# Length_Tuning_Routing_with_CM.net
KiCad netlist of a schematic drawn in Altium Designer
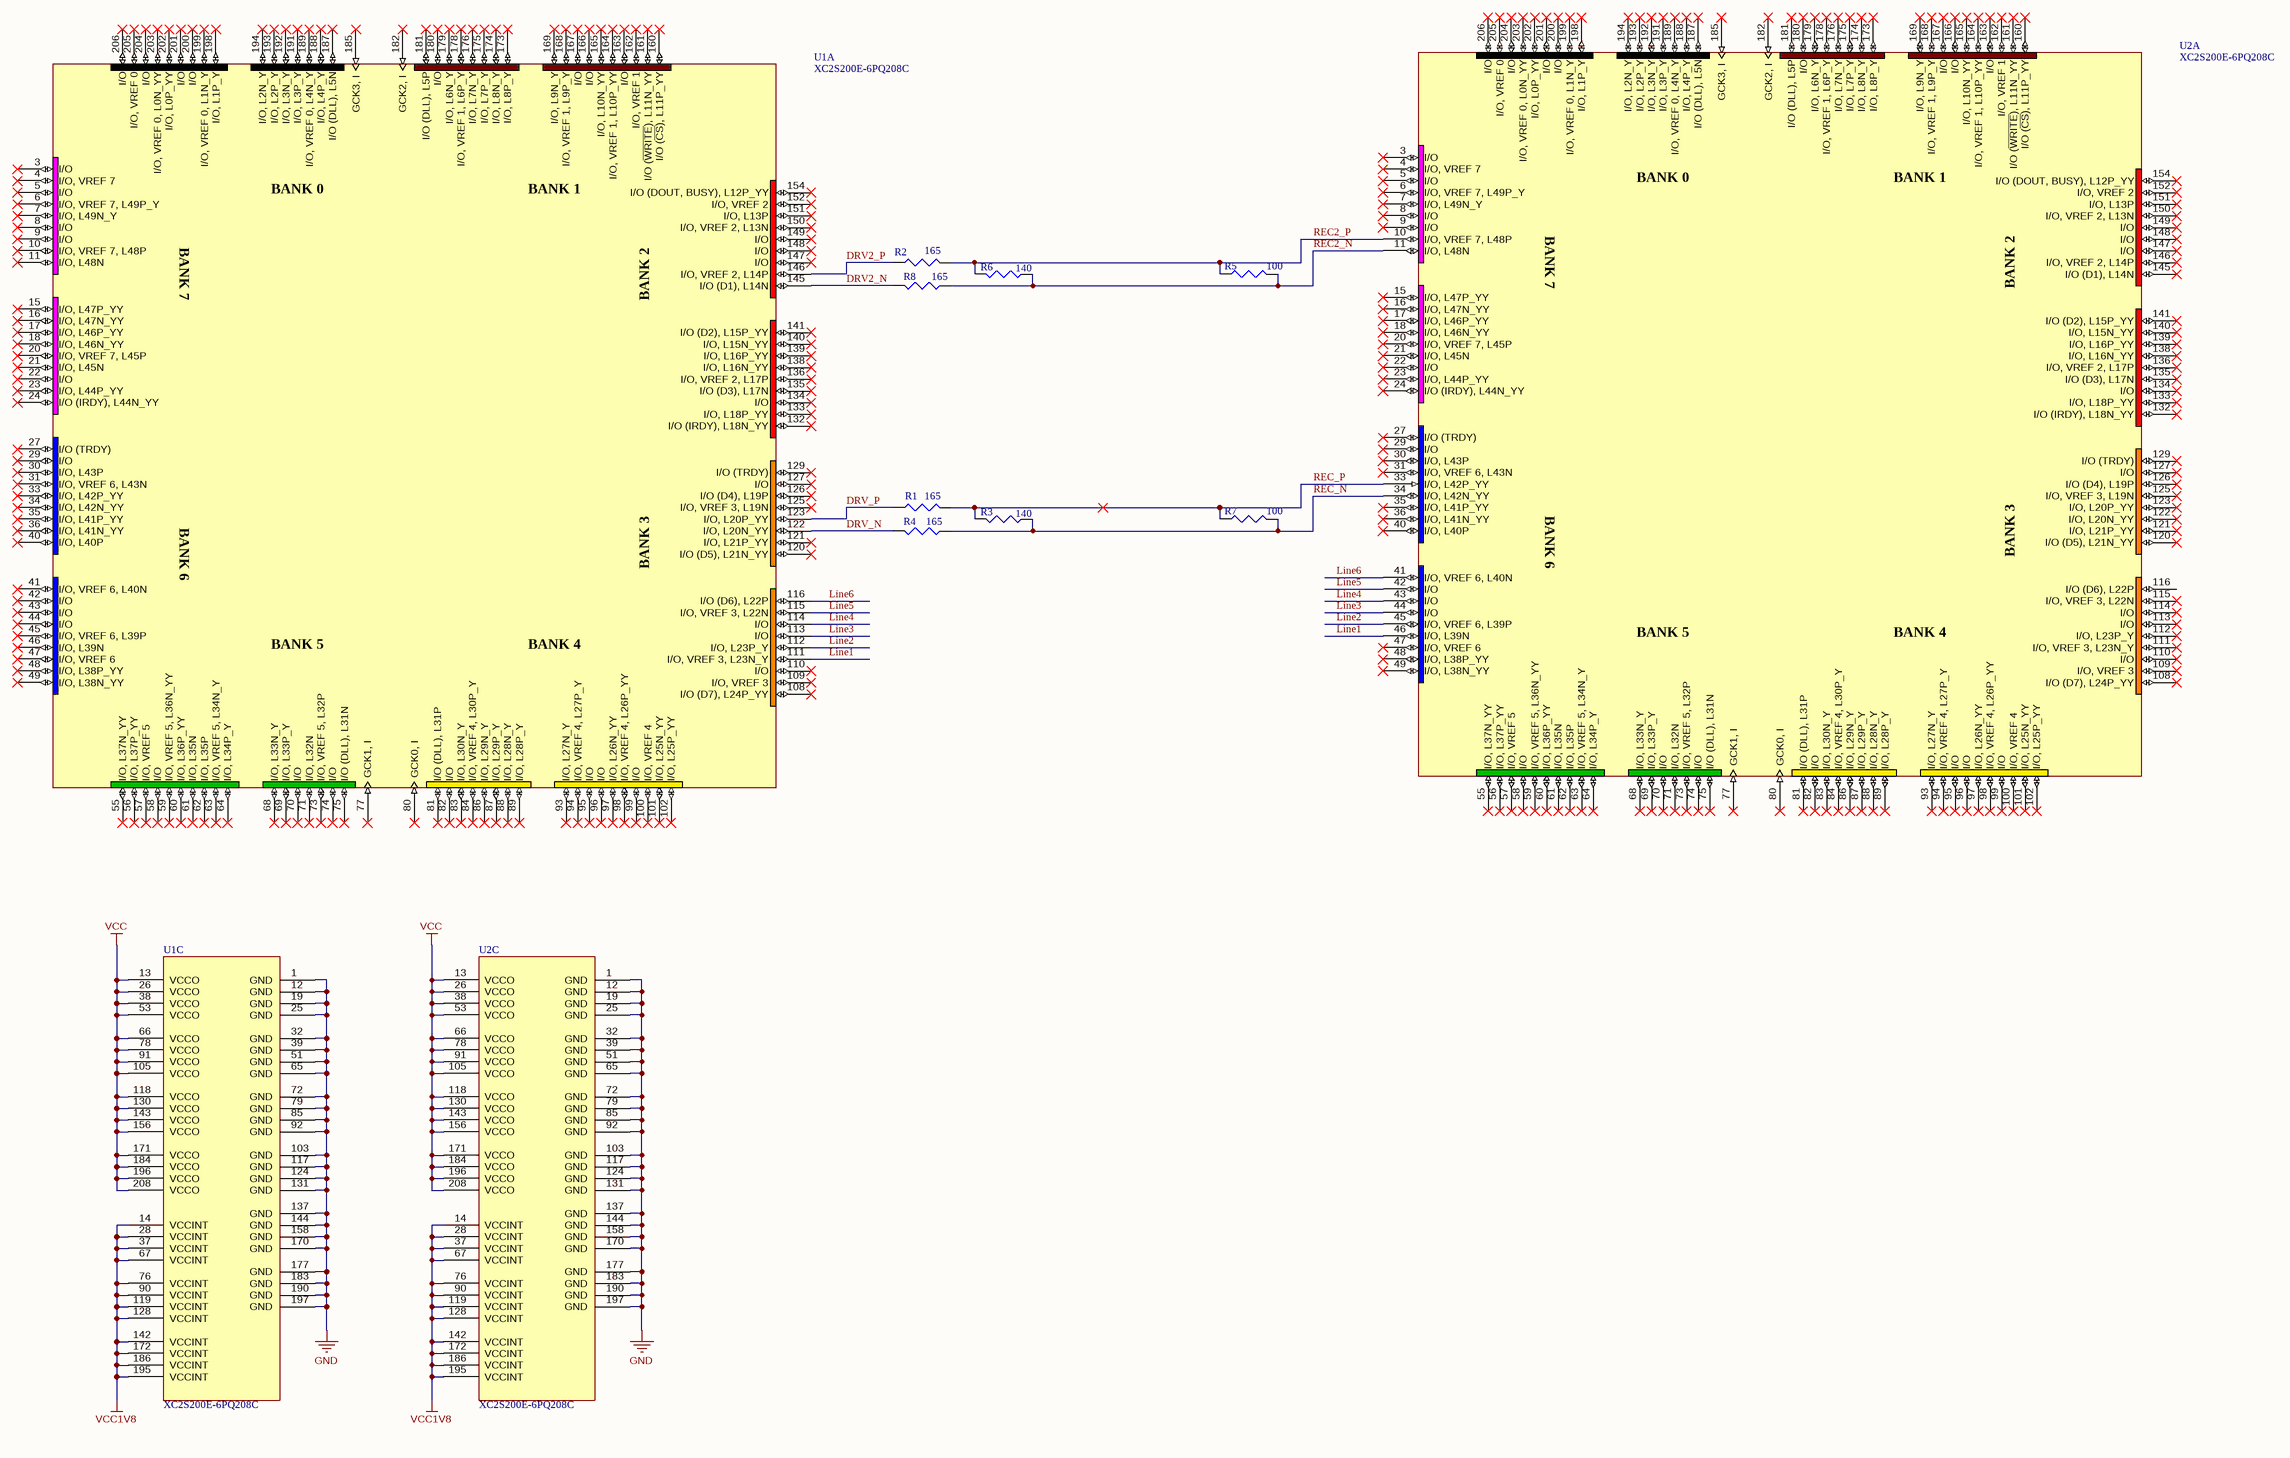
[diagram p0: Length Tuning Routing with CM.SchDoc]

(export (version "E")
  (design (tool "Eeschema 10.0.6"))
  (components
    (comp (ref "R1")
      (value "165")
      (footprint "J1-0603")
      (description "Resistor")
      (fields (field (name "Comment") "Res3") (field (name "PUBLISHER") "Altium Limited"))
      (libsource (lib "Miscellaneous Devices") (part "Res3"))
    )
    (comp (ref "R2")
      (value "165")
      (footprint "J1-0603")
      (description "Resistor")
      (fields (field (name "Comment") "Res3") (field (name "PUBLISHER") "Altium Limited"))
      (libsource (lib "Miscellaneous Devices") (part "Res3"))
    )
    (comp (ref "R3")
      (value "140")
      (footprint "J1-0603")
      (description "Resistor")
      (fields (field (name "Comment") "Res3") (field (name "PUBLISHER") "Altium Limited"))
      (libsource (lib "Miscellaneous Devices") (part "Res3"))
    )
    (comp (ref "R4")
      (value "165")
      (footprint "J1-0603")
      (description "Resistor")
      (fields (field (name "Comment") "Res3") (field (name "PUBLISHER") "Altium Limited"))
      (libsource (lib "Miscellaneous Devices") (part "Res3"))
    )
    (comp (ref "R5")
      (value "100")
      (footprint "J1-0603")
      (description "Resistor")
      (fields (field (name "Comment") "Res3") (field (name "PUBLISHER") "Altium Limited"))
      (libsource (lib "Miscellaneous Devices") (part "Res3"))
    )
    (comp (ref "R6")
      (value "140")
      (footprint "J1-0603")
      (description "Resistor")
      (fields (field (name "Comment") "Res3") (field (name "PUBLISHER") "Altium Limited"))
      (libsource (lib "Miscellaneous Devices") (part "Res3"))
    )
    (comp (ref "R7")
      (value "100")
      (footprint "J1-0603")
      (description "Resistor")
      (fields (field (name "Comment") "Res3") (field (name "PUBLISHER") "Altium Limited"))
      (libsource (lib "Miscellaneous Devices") (part "Res3"))
    )
    (comp (ref "R8")
      (value "165")
      (footprint "J1-0603")
      (description "Resistor")
      (fields (field (name "Comment") "Res3") (field (name "PUBLISHER") "Altium Limited"))
      (libsource (lib "Miscellaneous Devices") (part "Res3"))
    )
    (comp (ref "U1")
      (value "XC2S200E-6PQ208C")
      (footprint "PQ208")
      (description "Spartan-IIE 1.8V FPGA, 208-Pin PQFP, Standard Performance, Commercial Grade")
      (fields (field (name "PUBLISHER") "Altium Limited"))
      (libsource (lib "Xilinx Spartan-IIE") (part "XC2S200E-6PQ208C"))
    )
    (comp (ref "U2")
      (value "XC2S200E-6PQ208C")
      (footprint "PQ208")
      (description "Spartan-IIE 1.8V FPGA, 208-Pin PQFP, Standard Performance, Commercial Grade")
      (fields (field (name "PUBLISHER") "Altium Limited"))
      (libsource (lib "Xilinx Spartan-IIE") (part "XC2S200E-6PQ208C"))
    )
  )
  (nets
    (net (code "1") (name "/DRV2_N") (class "Default")
      (node (ref "R8") (pin "2") (pinfunction "2_2") (pintype "passive"))
      (node (ref "U1") (pin "145") (pinfunction "I/O_(D1),_L14N_145") (pintype "bidirectional"))
    )
    (net (code "2") (name "/DRV2_P") (class "Default")
      (node (ref "R2") (pin "1") (pinfunction "1_1") (pintype "passive"))
      (node (ref "U1") (pin "146") (pinfunction "I/O,_VREF_2,_L14P_146") (pintype "bidirectional"))
    )
    (net (code "3") (name "/DRV_N") (class "Default")
      (node (ref "R4") (pin "2") (pinfunction "2_2") (pintype "passive"))
      (node (ref "U1") (pin "122") (pinfunction "I/O,_L20N_YY_122") (pintype "bidirectional"))
    )
    (net (code "4") (name "/DRV_P") (class "Default")
      (node (ref "R1") (pin "1") (pinfunction "1_1") (pintype "passive"))
      (node (ref "U1") (pin "123") (pinfunction "I/O,_L20P_YY_123") (pintype "bidirectional"))
    )
    (net (code "5") (name "/Line1") (class "Default")
      (node (ref "U1") (pin "111") (pinfunction "I/O,_VREF_3,_L23N_Y_111") (pintype "bidirectional"))
      (node (ref "U2") (pin "46") (pinfunction "I/O,_L39N_46") (pintype "bidirectional"))
    )
    (net (code "6") (name "/Line2") (class "Default")
      (node (ref "U1") (pin "112") (pinfunction "I/O,_L23P_Y_112") (pintype "bidirectional"))
      (node (ref "U2") (pin "45") (pinfunction "I/O,_VREF_6,_L39P_45") (pintype "bidirectional"))
    )
    (net (code "7") (name "/Line3") (class "Default")
      (node (ref "U1") (pin "113") (pinfunction "I/O_113") (pintype "bidirectional"))
      (node (ref "U2") (pin "44") (pinfunction "I/O_44") (pintype "bidirectional"))
    )
    (net (code "8") (name "/Line4") (class "Default")
      (node (ref "U1") (pin "114") (pinfunction "I/O_114") (pintype "bidirectional"))
      (node (ref "U2") (pin "43") (pinfunction "I/O_43") (pintype "bidirectional"))
    )
    (net (code "9") (name "/Line5") (class "Default")
      (node (ref "U1") (pin "115") (pinfunction "I/O,_VREF_3,_L22N_115") (pintype "bidirectional"))
      (node (ref "U2") (pin "42") (pinfunction "I/O_42") (pintype "bidirectional"))
    )
    (net (code "10") (name "/Line6") (class "Default")
      (node (ref "U1") (pin "116") (pinfunction "I/O_(D6),_L22P_116") (pintype "bidirectional"))
      (node (ref "U2") (pin "41") (pinfunction "I/O,_VREF_6,_L40N_41") (pintype "bidirectional"))
    )
    (net (code "11") (name "/REC2_N") (class "Default")
      (node (ref "R5") (pin "2") (pinfunction "2_2") (pintype "passive"))
      (node (ref "R6") (pin "1") (pinfunction "1_1") (pintype "passive"))
      (node (ref "R8") (pin "1") (pinfunction "1_1") (pintype "passive"))
      (node (ref "U2") (pin "11") (pinfunction "I/O,_L48N_11") (pintype "bidirectional"))
    )
    (net (code "12") (name "/REC2_P") (class "Default")
      (node (ref "R2") (pin "2") (pinfunction "2_2") (pintype "passive"))
      (node (ref "R5") (pin "1") (pinfunction "1_1") (pintype "passive"))
      (node (ref "R6") (pin "2") (pinfunction "2_2") (pintype "passive"))
      (node (ref "U2") (pin "10") (pinfunction "I/O,_VREF_7,_L48P_10") (pintype "bidirectional"))
    )
    (net (code "13") (name "/REC_N") (class "Default")
      (node (ref "R3") (pin "1") (pinfunction "1_1") (pintype "passive"))
      (node (ref "R4") (pin "1") (pinfunction "1_1") (pintype "passive"))
      (node (ref "R7") (pin "2") (pinfunction "2_2") (pintype "passive"))
      (node (ref "U2") (pin "34") (pinfunction "I/O,_L42N_YY_34") (pintype "bidirectional"))
    )
    (net (code "14") (name "/REC_P") (class "Default")
      (node (ref "R1") (pin "2") (pinfunction "2_2") (pintype "passive"))
      (node (ref "R3") (pin "2") (pinfunction "2_2") (pintype "passive"))
      (node (ref "R7") (pin "1") (pinfunction "1_1") (pintype "passive"))
      (node (ref "U2") (pin "33") (pinfunction "I/O,_L42P_YY_33") (pintype "bidirectional"))
    )
    (net (code "15") (name "GND") (class "Default")
      (node (ref "U1") (pin "1") (pinfunction "GND_1") (pintype "power_in"))
      (node (ref "U1") (pin "103") (pinfunction "GND_103") (pintype "power_in"))
      (node (ref "U1") (pin "117") (pinfunction "GND_117") (pintype "power_in"))
      (node (ref "U1") (pin "12") (pinfunction "GND_12") (pintype "power_in"))
      (node (ref "U1") (pin "124") (pinfunction "GND_124") (pintype "power_in"))
      (node (ref "U1") (pin "131") (pinfunction "GND_131") (pintype "power_in"))
      (node (ref "U1") (pin "137") (pinfunction "GND_137") (pintype "power_in"))
      (node (ref "U1") (pin "144") (pinfunction "GND_144") (pintype "power_in"))
      (node (ref "U1") (pin "158") (pinfunction "GND_158") (pintype "power_in"))
      (node (ref "U1") (pin "170") (pinfunction "GND_170") (pintype "power_in"))
      (node (ref "U1") (pin "177") (pinfunction "GND_177") (pintype "power_in"))
      (node (ref "U1") (pin "183") (pinfunction "GND_183") (pintype "power_in"))
      (node (ref "U1") (pin "19") (pinfunction "GND_19") (pintype "power_in"))
      (node (ref "U1") (pin "190") (pinfunction "GND_190") (pintype "power_in"))
      (node (ref "U1") (pin "197") (pinfunction "GND_197") (pintype "power_in"))
      (node (ref "U1") (pin "25") (pinfunction "GND_25") (pintype "power_in"))
      (node (ref "U1") (pin "32") (pinfunction "GND_32") (pintype "power_in"))
      (node (ref "U1") (pin "39") (pinfunction "GND_39") (pintype "power_in"))
      (node (ref "U1") (pin "51") (pinfunction "GND_51") (pintype "power_in"))
      (node (ref "U1") (pin "65") (pinfunction "GND_65") (pintype "power_in"))
      (node (ref "U1") (pin "72") (pinfunction "GND_72") (pintype "power_in"))
      (node (ref "U1") (pin "79") (pinfunction "GND_79") (pintype "power_in"))
      (node (ref "U1") (pin "85") (pinfunction "GND_85") (pintype "power_in"))
      (node (ref "U1") (pin "92") (pinfunction "GND_92") (pintype "power_in"))
      (node (ref "U2") (pin "1") (pinfunction "GND_1") (pintype "power_in"))
      (node (ref "U2") (pin "103") (pinfunction "GND_103") (pintype "power_in"))
      (node (ref "U2") (pin "117") (pinfunction "GND_117") (pintype "power_in"))
      (node (ref "U2") (pin "12") (pinfunction "GND_12") (pintype "power_in"))
      (node (ref "U2") (pin "124") (pinfunction "GND_124") (pintype "power_in"))
      (node (ref "U2") (pin "131") (pinfunction "GND_131") (pintype "power_in"))
      (node (ref "U2") (pin "137") (pinfunction "GND_137") (pintype "power_in"))
      (node (ref "U2") (pin "144") (pinfunction "GND_144") (pintype "power_in"))
      (node (ref "U2") (pin "158") (pinfunction "GND_158") (pintype "power_in"))
      (node (ref "U2") (pin "170") (pinfunction "GND_170") (pintype "power_in"))
      (node (ref "U2") (pin "177") (pinfunction "GND_177") (pintype "power_in"))
      (node (ref "U2") (pin "183") (pinfunction "GND_183") (pintype "power_in"))
      (node (ref "U2") (pin "19") (pinfunction "GND_19") (pintype "power_in"))
      (node (ref "U2") (pin "190") (pinfunction "GND_190") (pintype "power_in"))
      (node (ref "U2") (pin "197") (pinfunction "GND_197") (pintype "power_in"))
      (node (ref "U2") (pin "25") (pinfunction "GND_25") (pintype "power_in"))
      (node (ref "U2") (pin "32") (pinfunction "GND_32") (pintype "power_in"))
      (node (ref "U2") (pin "39") (pinfunction "GND_39") (pintype "power_in"))
      (node (ref "U2") (pin "51") (pinfunction "GND_51") (pintype "power_in"))
      (node (ref "U2") (pin "65") (pinfunction "GND_65") (pintype "power_in"))
      (node (ref "U2") (pin "72") (pinfunction "GND_72") (pintype "power_in"))
      (node (ref "U2") (pin "79") (pinfunction "GND_79") (pintype "power_in"))
      (node (ref "U2") (pin "85") (pinfunction "GND_85") (pintype "power_in"))
      (node (ref "U2") (pin "92") (pinfunction "GND_92") (pintype "power_in"))
    )
    (net (code "16") (name "VCC") (class "Default")
      (node (ref "U1") (pin "105") (pinfunction "VCCO_105") (pintype "power_in"))
      (node (ref "U1") (pin "118") (pinfunction "VCCO_118") (pintype "power_in"))
      (node (ref "U1") (pin "13") (pinfunction "VCCO_13") (pintype "power_in"))
      (node (ref "U1") (pin "130") (pinfunction "VCCO_130") (pintype "power_in"))
      (node (ref "U1") (pin "143") (pinfunction "VCCO_143") (pintype "power_in"))
      (node (ref "U1") (pin "156") (pinfunction "VCCO_156") (pintype "power_in"))
      (node (ref "U1") (pin "171") (pinfunction "VCCO_171") (pintype "power_in"))
      (node (ref "U1") (pin "184") (pinfunction "VCCO_184") (pintype "power_in"))
      (node (ref "U1") (pin "196") (pinfunction "VCCO_196") (pintype "power_in"))
      (node (ref "U1") (pin "208") (pinfunction "VCCO_208") (pintype "power_in"))
      (node (ref "U1") (pin "26") (pinfunction "VCCO_26") (pintype "power_in"))
      (node (ref "U1") (pin "38") (pinfunction "VCCO_38") (pintype "power_in"))
      (node (ref "U1") (pin "53") (pinfunction "VCCO_53") (pintype "power_in"))
      (node (ref "U1") (pin "66") (pinfunction "VCCO_66") (pintype "power_in"))
      (node (ref "U1") (pin "78") (pinfunction "VCCO_78") (pintype "power_in"))
      (node (ref "U1") (pin "91") (pinfunction "VCCO_91") (pintype "power_in"))
      (node (ref "U2") (pin "105") (pinfunction "VCCO_105") (pintype "power_in"))
      (node (ref "U2") (pin "118") (pinfunction "VCCO_118") (pintype "power_in"))
      (node (ref "U2") (pin "13") (pinfunction "VCCO_13") (pintype "power_in"))
      (node (ref "U2") (pin "130") (pinfunction "VCCO_130") (pintype "power_in"))
      (node (ref "U2") (pin "143") (pinfunction "VCCO_143") (pintype "power_in"))
      (node (ref "U2") (pin "156") (pinfunction "VCCO_156") (pintype "power_in"))
      (node (ref "U2") (pin "171") (pinfunction "VCCO_171") (pintype "power_in"))
      (node (ref "U2") (pin "184") (pinfunction "VCCO_184") (pintype "power_in"))
      (node (ref "U2") (pin "196") (pinfunction "VCCO_196") (pintype "power_in"))
      (node (ref "U2") (pin "208") (pinfunction "VCCO_208") (pintype "power_in"))
      (node (ref "U2") (pin "26") (pinfunction "VCCO_26") (pintype "power_in"))
      (node (ref "U2") (pin "38") (pinfunction "VCCO_38") (pintype "power_in"))
      (node (ref "U2") (pin "53") (pinfunction "VCCO_53") (pintype "power_in"))
      (node (ref "U2") (pin "66") (pinfunction "VCCO_66") (pintype "power_in"))
      (node (ref "U2") (pin "78") (pinfunction "VCCO_78") (pintype "power_in"))
      (node (ref "U2") (pin "91") (pinfunction "VCCO_91") (pintype "power_in"))
    )
    (net (code "17") (name "VCC1V8") (class "Default")
      (node (ref "U1") (pin "119") (pinfunction "VCCINT_119") (pintype "power_in"))
      (node (ref "U1") (pin "128") (pinfunction "VCCINT_128") (pintype "power_in"))
      (node (ref "U1") (pin "14") (pinfunction "VCCINT_14") (pintype "power_in"))
      (node (ref "U1") (pin "142") (pinfunction "VCCINT_142") (pintype "power_in"))
      (node (ref "U1") (pin "172") (pinfunction "VCCINT_172") (pintype "power_in"))
      (node (ref "U1") (pin "186") (pinfunction "VCCINT_186") (pintype "power_in"))
      (node (ref "U1") (pin "195") (pinfunction "VCCINT_195") (pintype "power_in"))
      (node (ref "U1") (pin "28") (pinfunction "VCCINT_28") (pintype "power_in"))
      (node (ref "U1") (pin "37") (pinfunction "VCCINT_37") (pintype "power_in"))
      (node (ref "U1") (pin "67") (pinfunction "VCCINT_67") (pintype "power_in"))
      (node (ref "U1") (pin "76") (pinfunction "VCCINT_76") (pintype "power_in"))
      (node (ref "U1") (pin "90") (pinfunction "VCCINT_90") (pintype "power_in"))
      (node (ref "U2") (pin "119") (pinfunction "VCCINT_119") (pintype "power_in"))
      (node (ref "U2") (pin "128") (pinfunction "VCCINT_128") (pintype "power_in"))
      (node (ref "U2") (pin "14") (pinfunction "VCCINT_14") (pintype "power_in"))
      (node (ref "U2") (pin "142") (pinfunction "VCCINT_142") (pintype "power_in"))
      (node (ref "U2") (pin "172") (pinfunction "VCCINT_172") (pintype "power_in"))
      (node (ref "U2") (pin "186") (pinfunction "VCCINT_186") (pintype "power_in"))
      (node (ref "U2") (pin "195") (pinfunction "VCCINT_195") (pintype "power_in"))
      (node (ref "U2") (pin "28") (pinfunction "VCCINT_28") (pintype "power_in"))
      (node (ref "U2") (pin "37") (pinfunction "VCCINT_37") (pintype "power_in"))
      (node (ref "U2") (pin "67") (pinfunction "VCCINT_67") (pintype "power_in"))
      (node (ref "U2") (pin "76") (pinfunction "VCCINT_76") (pintype "power_in"))
      (node (ref "U2") (pin "90") (pinfunction "VCCINT_90") (pintype "power_in"))
    )
    (net (code "18") (name "unconnected-(U1A-GCK0,_I-Pad80)") (class "Default")
      (node (ref "U1") (pin "80") (pinfunction "GCK0,_I_80") (pintype "input+no_connect"))
    )
    (net (code "19") (name "unconnected-(U1A-GCK1,_I-Pad77)") (class "Default")
      (node (ref "U1") (pin "77") (pinfunction "GCK1,_I_77") (pintype "input+no_connect"))
    )
    (net (code "20") (name "unconnected-(U1A-GCK2,_I-Pad182)") (class "Default")
      (node (ref "U1") (pin "182") (pinfunction "GCK2,_I_182") (pintype "input+no_connect"))
    )
    (net (code "21") (name "unconnected-(U1A-GCK3,_I-Pad185)") (class "Default")
      (node (ref "U1") (pin "185") (pinfunction "GCK3,_I_185") (pintype "input+no_connect"))
    )
    (net (code "22") (name "unconnected-(U1A-I{slash}O,_L0P_YY-Pad202)") (class "Default")
      (node (ref "U1") (pin "202") (pinfunction "I/O,_L0P_YY_202") (pintype "bidirectional+no_connect"))
    )
    (net (code "23") (name "unconnected-(U1A-I{slash}O,_L1P_Y-Pad198)") (class "Default")
      (node (ref "U1") (pin "198") (pinfunction "I/O,_L1P_Y_198") (pintype "bidirectional+no_connect"))
    )
    (net (code "24") (name "unconnected-(U1A-I{slash}O,_L2N_Y-Pad194)") (class "Default")
      (node (ref "U1") (pin "194") (pinfunction "I/O,_L2N_Y_194") (pintype "bidirectional+no_connect"))
    )
    (net (code "25") (name "unconnected-(U1A-I{slash}O,_L2P_Y-Pad193)") (class "Default")
      (node (ref "U1") (pin "193") (pinfunction "I/O,_L2P_Y_193") (pintype "bidirectional+no_connect"))
    )
    (net (code "26") (name "unconnected-(U1A-I{slash}O,_L3N_Y-Pad192)") (class "Default")
      (node (ref "U1") (pin "192") (pinfunction "I/O,_L3N_Y_192") (pintype "bidirectional+no_connect"))
    )
    (net (code "27") (name "unconnected-(U1A-I{slash}O,_L3P_Y-Pad191)") (class "Default")
      (node (ref "U1") (pin "191") (pinfunction "I/O,_L3P_Y_191") (pintype "bidirectional+no_connect"))
    )
    (net (code "28") (name "unconnected-(U1A-I{slash}O,_L4P_Y-Pad188)") (class "Default")
      (node (ref "U1") (pin "188") (pinfunction "I/O,_L4P_Y_188") (pintype "bidirectional+no_connect"))
    )
    (net (code "29") (name "unconnected-(U1A-I{slash}O,_L6N_Y-Pad179)") (class "Default")
      (node (ref "U1") (pin "179") (pinfunction "I/O,_L6N_Y_179") (pintype "bidirectional+no_connect"))
    )
    (net (code "30") (name "unconnected-(U1A-I{slash}O,_L7N_Y-Pad176)") (class "Default")
      (node (ref "U1") (pin "176") (pinfunction "I/O,_L7N_Y_176") (pintype "bidirectional+no_connect"))
    )
    (net (code "31") (name "unconnected-(U1A-I{slash}O,_L7P_Y-Pad175)") (class "Default")
      (node (ref "U1") (pin "175") (pinfunction "I/O,_L7P_Y_175") (pintype "bidirectional+no_connect"))
    )
    (net (code "32") (name "unconnected-(U1A-I{slash}O,_L8N_Y-Pad174)") (class "Default")
      (node (ref "U1") (pin "174") (pinfunction "I/O,_L8N_Y_174") (pintype "bidirectional+no_connect"))
    )
    (net (code "33") (name "unconnected-(U1A-I{slash}O,_L8P_Y-Pad173)") (class "Default")
      (node (ref "U1") (pin "173") (pinfunction "I/O,_L8P_Y_173") (pintype "bidirectional+no_connect"))
    )
    (net (code "34") (name "unconnected-(U1A-I{slash}O,_L9N_Y-Pad169)") (class "Default")
      (node (ref "U1") (pin "169") (pinfunction "I/O,_L9N_Y_169") (pintype "bidirectional+no_connect"))
    )
    (net (code "35") (name "unconnected-(U1A-I{slash}O,_L10N_YY-Pad165)") (class "Default")
      (node (ref "U1") (pin "165") (pinfunction "I/O,_L10N_YY_165") (pintype "bidirectional+no_connect"))
    )
    (net (code "36") (name "unconnected-(U1A-I{slash}O,_L13P-Pad151)") (class "Default")
      (node (ref "U1") (pin "151") (pinfunction "I/O,_L13P_151") (pintype "bidirectional+no_connect"))
    )
    (net (code "37") (name "unconnected-(U1A-I{slash}O,_L15N_YY-Pad140)") (class "Default")
      (node (ref "U1") (pin "140") (pinfunction "I/O,_L15N_YY_140") (pintype "bidirectional+no_connect"))
    )
    (net (code "38") (name "unconnected-(U1A-I{slash}O,_L16N_YY-Pad138)") (class "Default")
      (node (ref "U1") (pin "138") (pinfunction "I/O,_L16N_YY_138") (pintype "bidirectional+no_connect"))
    )
    (net (code "39") (name "unconnected-(U1A-I{slash}O,_L16P_YY-Pad139)") (class "Default")
      (node (ref "U1") (pin "139") (pinfunction "I/O,_L16P_YY_139") (pintype "bidirectional+no_connect"))
    )
    (net (code "40") (name "unconnected-(U1A-I{slash}O,_L18P_YY-Pad133)") (class "Default")
      (node (ref "U1") (pin "133") (pinfunction "I/O,_L18P_YY_133") (pintype "bidirectional+no_connect"))
    )
    (net (code "41") (name "unconnected-(U1A-I{slash}O,_L21P_YY-Pad121)") (class "Default")
      (node (ref "U1") (pin "121") (pinfunction "I/O,_L21P_YY_121") (pintype "bidirectional+no_connect"))
    )
    (net (code "42") (name "unconnected-(U1A-I{slash}O,_L25N_YY-Pad101)") (class "Default")
      (node (ref "U1") (pin "101") (pinfunction "I/O,_L25N_YY_101") (pintype "bidirectional+no_connect"))
    )
    (net (code "43") (name "unconnected-(U1A-I{slash}O,_L25P_YY-Pad102)") (class "Default")
      (node (ref "U1") (pin "102") (pinfunction "I/O,_L25P_YY_102") (pintype "bidirectional+no_connect"))
    )
    (net (code "44") (name "unconnected-(U1A-I{slash}O,_L26N_YY-Pad97)") (class "Default")
      (node (ref "U1") (pin "97") (pinfunction "I/O,_L26N_YY_97") (pintype "bidirectional+no_connect"))
    )
    (net (code "45") (name "unconnected-(U1A-I{slash}O,_L27N_Y-Pad93)") (class "Default")
      (node (ref "U1") (pin "93") (pinfunction "I/O,_L27N_Y_93") (pintype "bidirectional+no_connect"))
    )
    (net (code "46") (name "unconnected-(U1A-I{slash}O,_L28N_Y-Pad88)") (class "Default")
      (node (ref "U1") (pin "88") (pinfunction "I/O,_L28N_Y_88") (pintype "bidirectional+no_connect"))
    )
    (net (code "47") (name "unconnected-(U1A-I{slash}O,_L28P_Y-Pad89)") (class "Default")
      (node (ref "U1") (pin "89") (pinfunction "I/O,_L28P_Y_89") (pintype "bidirectional+no_connect"))
    )
    (net (code "48") (name "unconnected-(U1A-I{slash}O,_L29N_Y-Pad86)") (class "Default")
      (node (ref "U1") (pin "86") (pinfunction "I/O,_L29N_Y_86") (pintype "bidirectional+no_connect"))
    )
    (net (code "49") (name "unconnected-(U1A-I{slash}O,_L29P_Y-Pad87)") (class "Default")
      (node (ref "U1") (pin "87") (pinfunction "I/O,_L29P_Y_87") (pintype "bidirectional+no_connect"))
    )
    (net (code "50") (name "unconnected-(U1A-I{slash}O,_L30N_Y-Pad83)") (class "Default")
      (node (ref "U1") (pin "83") (pinfunction "I/O,_L30N_Y_83") (pintype "bidirectional+no_connect"))
    )
    (net (code "51") (name "unconnected-(U1A-I{slash}O,_L32N-Pad71)") (class "Default")
      (node (ref "U1") (pin "71") (pinfunction "I/O,_L32N_71") (pintype "bidirectional+no_connect"))
    )
    (net (code "52") (name "unconnected-(U1A-I{slash}O,_L33N_Y-Pad68)") (class "Default")
      (node (ref "U1") (pin "68") (pinfunction "I/O,_L33N_Y_68") (pintype "bidirectional+no_connect"))
    )
    (net (code "53") (name "unconnected-(U1A-I{slash}O,_L33P_Y-Pad69)") (class "Default")
      (node (ref "U1") (pin "69") (pinfunction "I/O,_L33P_Y_69") (pintype "bidirectional+no_connect"))
    )
    (net (code "54") (name "unconnected-(U1A-I{slash}O,_L34P_Y-Pad64)") (class "Default")
      (node (ref "U1") (pin "64") (pinfunction "I/O,_L34P_Y_64") (pintype "bidirectional+no_connect"))
    )
    (net (code "55") (name "unconnected-(U1A-I{slash}O,_L35N-Pad61)") (class "Default")
      (node (ref "U1") (pin "61") (pinfunction "I/O,_L35N_61") (pintype "bidirectional+no_connect"))
    )
    (net (code "56") (name "unconnected-(U1A-I{slash}O,_L35P-Pad62)") (class "Default")
      (node (ref "U1") (pin "62") (pinfunction "I/O,_L35P_62") (pintype "bidirectional+no_connect"))
    )
    (net (code "57") (name "unconnected-(U1A-I{slash}O,_L36P_YY-Pad60)") (class "Default")
      (node (ref "U1") (pin "60") (pinfunction "I/O,_L36P_YY_60") (pintype "bidirectional+no_connect"))
    )
    (net (code "58") (name "unconnected-(U1A-I{slash}O,_L37N_YY-Pad55)") (class "Default")
      (node (ref "U1") (pin "55") (pinfunction "I/O,_L37N_YY_55") (pintype "bidirectional+no_connect"))
    )
    (net (code "59") (name "unconnected-(U1A-I{slash}O,_L37P_YY-Pad56)") (class "Default")
      (node (ref "U1") (pin "56") (pinfunction "I/O,_L37P_YY_56") (pintype "bidirectional+no_connect"))
    )
    (net (code "60") (name "unconnected-(U1A-I{slash}O,_L38N_YY-Pad49)") (class "Default")
      (node (ref "U1") (pin "49") (pinfunction "I/O,_L38N_YY_49") (pintype "bidirectional+no_connect"))
    )
    (net (code "61") (name "unconnected-(U1A-I{slash}O,_L38P_YY-Pad48)") (class "Default")
      (node (ref "U1") (pin "48") (pinfunction "I/O,_L38P_YY_48") (pintype "bidirectional+no_connect"))
    )
    (net (code "62") (name "unconnected-(U1A-I{slash}O,_L39N-Pad46)") (class "Default")
      (node (ref "U1") (pin "46") (pinfunction "I/O,_L39N_46") (pintype "bidirectional+no_connect"))
    )
    (net (code "63") (name "unconnected-(U1A-I{slash}O,_L40P-Pad40)") (class "Default")
      (node (ref "U1") (pin "40") (pinfunction "I/O,_L40P_40") (pintype "bidirectional+no_connect"))
    )
    (net (code "64") (name "unconnected-(U1A-I{slash}O,_L41N_YY-Pad36)") (class "Default")
      (node (ref "U1") (pin "36") (pinfunction "I/O,_L41N_YY_36") (pintype "bidirectional+no_connect"))
    )
    (net (code "65") (name "unconnected-(U1A-I{slash}O,_L41P_YY-Pad35)") (class "Default")
      (node (ref "U1") (pin "35") (pinfunction "I/O,_L41P_YY_35") (pintype "bidirectional+no_connect"))
    )
    (net (code "66") (name "unconnected-(U1A-I{slash}O,_L42N_YY-Pad34)") (class "Default")
      (node (ref "U1") (pin "34") (pinfunction "I/O,_L42N_YY_34") (pintype "bidirectional+no_connect"))
    )
    (net (code "67") (name "unconnected-(U1A-I{slash}O,_L42P_YY-Pad33)") (class "Default")
      (node (ref "U1") (pin "33") (pinfunction "I/O,_L42P_YY_33") (pintype "bidirectional+no_connect"))
    )
    (net (code "68") (name "unconnected-(U1A-I{slash}O,_L43P-Pad30)") (class "Default")
      (node (ref "U1") (pin "30") (pinfunction "I/O,_L43P_30") (pintype "bidirectional+no_connect"))
    )
    (net (code "69") (name "unconnected-(U1A-I{slash}O,_L44P_YY-Pad23)") (class "Default")
      (node (ref "U1") (pin "23") (pinfunction "I/O,_L44P_YY_23") (pintype "bidirectional+no_connect"))
    )
    (net (code "70") (name "unconnected-(U1A-I{slash}O,_L45N-Pad21)") (class "Default")
      (node (ref "U1") (pin "21") (pinfunction "I/O,_L45N_21") (pintype "bidirectional+no_connect"))
    )
    (net (code "71") (name "unconnected-(U1A-I{slash}O,_L46N_YY-Pad18)") (class "Default")
      (node (ref "U1") (pin "18") (pinfunction "I/O,_L46N_YY_18") (pintype "bidirectional+no_connect"))
    )
    (net (code "72") (name "unconnected-(U1A-I{slash}O,_L46P_YY-Pad17)") (class "Default")
      (node (ref "U1") (pin "17") (pinfunction "I/O,_L46P_YY_17") (pintype "bidirectional+no_connect"))
    )
    (net (code "73") (name "unconnected-(U1A-I{slash}O,_L47N_YY-Pad16)") (class "Default")
      (node (ref "U1") (pin "16") (pinfunction "I/O,_L47N_YY_16") (pintype "bidirectional+no_connect"))
    )
    (net (code "74") (name "unconnected-(U1A-I{slash}O,_L47P_YY-Pad15)") (class "Default")
      (node (ref "U1") (pin "15") (pinfunction "I/O,_L47P_YY_15") (pintype "bidirectional+no_connect"))
    )
    (net (code "75") (name "unconnected-(U1A-I{slash}O,_L48N-Pad11)") (class "Default")
      (node (ref "U1") (pin "11") (pinfunction "I/O,_L48N_11") (pintype "bidirectional+no_connect"))
    )
    (net (code "76") (name "unconnected-(U1A-I{slash}O,_L49N_Y-Pad7)") (class "Default")
      (node (ref "U1") (pin "7") (pinfunction "I/O,_L49N_Y_7") (pintype "bidirectional+no_connect"))
    )
    (net (code "77") (name "unconnected-(U1A-I{slash}O,_VREF_0,_L0N_YY-Pad203)") (class "Default")
      (node (ref "U1") (pin "203") (pinfunction "I/O,_VREF_0,_L0N_YY_203") (pintype "bidirectional+no_connect"))
    )
    (net (code "78") (name "unconnected-(U1A-I{slash}O,_VREF_0,_L1N_Y-Pad199)") (class "Default")
      (node (ref "U1") (pin "199") (pinfunction "I/O,_VREF_0,_L1N_Y_199") (pintype "bidirectional+no_connect"))
    )
    (net (code "79") (name "unconnected-(U1A-I{slash}O,_VREF_0,_L4N_Y-Pad189)") (class "Default")
      (node (ref "U1") (pin "189") (pinfunction "I/O,_VREF_0,_L4N_Y_189") (pintype "bidirectional+no_connect"))
    )
    (net (code "80") (name "unconnected-(U1A-I{slash}O,_VREF_0-Pad205)") (class "Default")
      (node (ref "U1") (pin "205") (pinfunction "I/O,_VREF_0_205") (pintype "bidirectional+no_connect"))
    )
    (net (code "81") (name "unconnected-(U1A-I{slash}O,_VREF_1,_L6P_Y-Pad178)") (class "Default")
      (node (ref "U1") (pin "178") (pinfunction "I/O,_VREF_1,_L6P_Y_178") (pintype "bidirectional+no_connect"))
    )
    (net (code "82") (name "unconnected-(U1A-I{slash}O,_VREF_1,_L9P_Y-Pad168)") (class "Default")
      (node (ref "U1") (pin "168") (pinfunction "I/O,_VREF_1,_L9P_Y_168") (pintype "bidirectional+no_connect"))
    )
    (net (code "83") (name "unconnected-(U1A-I{slash}O,_VREF_1,_L10P_YY-Pad164)") (class "Default")
      (node (ref "U1") (pin "164") (pinfunction "I/O,_VREF_1,_L10P_YY_164") (pintype "bidirectional+no_connect"))
    )
    (net (code "84") (name "unconnected-(U1A-I{slash}O,_VREF_1-Pad162)") (class "Default")
      (node (ref "U1") (pin "162") (pinfunction "I/O,_VREF_1_162") (pintype "bidirectional+no_connect"))
    )
    (net (code "85") (name "unconnected-(U1A-I{slash}O,_VREF_2,_L13N-Pad150)") (class "Default")
      (node (ref "U1") (pin "150") (pinfunction "I/O,_VREF_2,_L13N_150") (pintype "bidirectional+no_connect"))
    )
    (net (code "86") (name "unconnected-(U1A-I{slash}O,_VREF_2,_L17P-Pad136)") (class "Default")
      (node (ref "U1") (pin "136") (pinfunction "I/O,_VREF_2,_L17P_136") (pintype "bidirectional+no_connect"))
    )
    (net (code "87") (name "unconnected-(U1A-I{slash}O,_VREF_2-Pad152)") (class "Default")
      (node (ref "U1") (pin "152") (pinfunction "I/O,_VREF_2_152") (pintype "bidirectional+no_connect"))
    )
    (net (code "88") (name "unconnected-(U1A-I{slash}O,_VREF_3,_L19N-Pad125)") (class "Default")
      (node (ref "U1") (pin "125") (pinfunction "I/O,_VREF_3,_L19N_125") (pintype "bidirectional+no_connect"))
    )
    (net (code "89") (name "unconnected-(U1A-I{slash}O,_VREF_3-Pad109)") (class "Default")
      (node (ref "U1") (pin "109") (pinfunction "I/O,_VREF_3_109") (pintype "bidirectional+no_connect"))
    )
    (net (code "90") (name "unconnected-(U1A-I{slash}O,_VREF_4,_L26P_YY-Pad98)") (class "Default")
      (node (ref "U1") (pin "98") (pinfunction "I/O,_VREF_4,_L26P_YY_98") (pintype "bidirectional+no_connect"))
    )
    (net (code "91") (name "unconnected-(U1A-I{slash}O,_VREF_4,_L27P_Y-Pad94)") (class "Default")
      (node (ref "U1") (pin "94") (pinfunction "I/O,_VREF_4,_L27P_Y_94") (pintype "bidirectional+no_connect"))
    )
    (net (code "92") (name "unconnected-(U1A-I{slash}O,_VREF_4,_L30P_Y-Pad84)") (class "Default")
      (node (ref "U1") (pin "84") (pinfunction "I/O,_VREF_4,_L30P_Y_84") (pintype "bidirectional+no_connect"))
    )
    (net (code "93") (name "unconnected-(U1A-I{slash}O,_VREF_4-Pad100)") (class "Default")
      (node (ref "U1") (pin "100") (pinfunction "I/O,_VREF_4_100") (pintype "bidirectional+no_connect"))
    )
    (net (code "94") (name "unconnected-(U1A-I{slash}O,_VREF_5,_L32P-Pad73)") (class "Default")
      (node (ref "U1") (pin "73") (pinfunction "I/O,_VREF_5,_L32P_73") (pintype "bidirectional+no_connect"))
    )
    (net (code "95") (name "unconnected-(U1A-I{slash}O,_VREF_5,_L34N_Y-Pad63)") (class "Default")
      (node (ref "U1") (pin "63") (pinfunction "I/O,_VREF_5,_L34N_Y_63") (pintype "bidirectional+no_connect"))
    )
    (net (code "96") (name "unconnected-(U1A-I{slash}O,_VREF_5,_L36N_YY-Pad59)") (class "Default")
      (node (ref "U1") (pin "59") (pinfunction "I/O,_VREF_5,_L36N_YY_59") (pintype "bidirectional+no_connect"))
    )
    (net (code "97") (name "unconnected-(U1A-I{slash}O,_VREF_5-Pad57)") (class "Default")
      (node (ref "U1") (pin "57") (pinfunction "I/O,_VREF_5_57") (pintype "bidirectional+no_connect"))
    )
    (net (code "98") (name "unconnected-(U1A-I{slash}O,_VREF_6,_L39P-Pad45)") (class "Default")
      (node (ref "U1") (pin "45") (pinfunction "I/O,_VREF_6,_L39P_45") (pintype "bidirectional+no_connect"))
    )
    (net (code "99") (name "unconnected-(U1A-I{slash}O,_VREF_6,_L40N-Pad41)") (class "Default")
      (node (ref "U1") (pin "41") (pinfunction "I/O,_VREF_6,_L40N_41") (pintype "bidirectional+no_connect"))
    )
    (net (code "100") (name "unconnected-(U1A-I{slash}O,_VREF_6,_L43N-Pad31)") (class "Default")
      (node (ref "U1") (pin "31") (pinfunction "I/O,_VREF_6,_L43N_31") (pintype "bidirectional+no_connect"))
    )
    (net (code "101") (name "unconnected-(U1A-I{slash}O,_VREF_6-Pad47)") (class "Default")
      (node (ref "U1") (pin "47") (pinfunction "I/O,_VREF_6_47") (pintype "bidirectional+no_connect"))
    )
    (net (code "102") (name "unconnected-(U1A-I{slash}O,_VREF_7,_L45P-Pad20)") (class "Default")
      (node (ref "U1") (pin "20") (pinfunction "I/O,_VREF_7,_L45P_20") (pintype "bidirectional+no_connect"))
    )
    (net (code "103") (name "unconnected-(U1A-I{slash}O,_VREF_7,_L48P-Pad10)") (class "Default")
      (node (ref "U1") (pin "10") (pinfunction "I/O,_VREF_7,_L48P_10") (pintype "bidirectional+no_connect"))
    )
    (net (code "104") (name "unconnected-(U1A-I{slash}O,_VREF_7,_L49P_Y-Pad6)") (class "Default")
      (node (ref "U1") (pin "6") (pinfunction "I/O,_VREF_7,_L49P_Y_6") (pintype "bidirectional+no_connect"))
    )
    (net (code "105") (name "unconnected-(U1A-I{slash}O,_VREF_7-Pad4)") (class "Default")
      (node (ref "U1") (pin "4") (pinfunction "I/O,_VREF_7_4") (pintype "bidirectional+no_connect"))
    )
    (net (code "106") (name "unconnected-(U1A-I{slash}O-Pad3)") (class "Default")
      (node (ref "U1") (pin "3") (pinfunction "I/O_3") (pintype "bidirectional+no_connect"))
    )
    (net (code "107") (name "unconnected-(U1A-I{slash}O-Pad5)") (class "Default")
      (node (ref "U1") (pin "5") (pinfunction "I/O_5") (pintype "bidirectional+no_connect"))
    )
    (net (code "108") (name "unconnected-(U1A-I{slash}O-Pad8)") (class "Default")
      (node (ref "U1") (pin "8") (pinfunction "I/O_8") (pintype "bidirectional+no_connect"))
    )
    (net (code "109") (name "unconnected-(U1A-I{slash}O-Pad9)") (class "Default")
      (node (ref "U1") (pin "9") (pinfunction "I/O_9") (pintype "bidirectional+no_connect"))
    )
    (net (code "110") (name "unconnected-(U1A-I{slash}O-Pad22)") (class "Default")
      (node (ref "U1") (pin "22") (pinfunction "I/O_22") (pintype "bidirectional+no_connect"))
    )
    (net (code "111") (name "unconnected-(U1A-I{slash}O-Pad29)") (class "Default")
      (node (ref "U1") (pin "29") (pinfunction "I/O_29") (pintype "bidirectional+no_connect"))
    )
    (net (code "112") (name "unconnected-(U1A-I{slash}O-Pad42)") (class "Default")
      (node (ref "U1") (pin "42") (pinfunction "I/O_42") (pintype "bidirectional+no_connect"))
    )
    (net (code "113") (name "unconnected-(U1A-I{slash}O-Pad43)") (class "Default")
      (node (ref "U1") (pin "43") (pinfunction "I/O_43") (pintype "bidirectional+no_connect"))
    )
    (net (code "114") (name "unconnected-(U1A-I{slash}O-Pad44)") (class "Default")
      (node (ref "U1") (pin "44") (pinfunction "I/O_44") (pintype "bidirectional+no_connect"))
    )
    (net (code "115") (name "unconnected-(U1A-I{slash}O-Pad58)") (class "Default")
      (node (ref "U1") (pin "58") (pinfunction "I/O_58") (pintype "bidirectional+no_connect"))
    )
    (net (code "116") (name "unconnected-(U1A-I{slash}O-Pad70)") (class "Default")
      (node (ref "U1") (pin "70") (pinfunction "I/O_70") (pintype "bidirectional+no_connect"))
    )
    (net (code "117") (name "unconnected-(U1A-I{slash}O-Pad74)") (class "Default")
      (node (ref "U1") (pin "74") (pinfunction "I/O_74") (pintype "bidirectional+no_connect"))
    )
    (net (code "118") (name "unconnected-(U1A-I{slash}O-Pad82)") (class "Default")
      (node (ref "U1") (pin "82") (pinfunction "I/O_82") (pintype "bidirectional+no_connect"))
    )
    (net (code "119") (name "unconnected-(U1A-I{slash}O-Pad95)") (class "Default")
      (node (ref "U1") (pin "95") (pinfunction "I/O_95") (pintype "bidirectional+no_connect"))
    )
    (net (code "120") (name "unconnected-(U1A-I{slash}O-Pad96)") (class "Default")
      (node (ref "U1") (pin "96") (pinfunction "I/O_96") (pintype "bidirectional+no_connect"))
    )
    (net (code "121") (name "unconnected-(U1A-I{slash}O-Pad99)") (class "Default")
      (node (ref "U1") (pin "99") (pinfunction "I/O_99") (pintype "bidirectional+no_connect"))
    )
    (net (code "122") (name "unconnected-(U1A-I{slash}O-Pad110)") (class "Default")
      (node (ref "U1") (pin "110") (pinfunction "I/O_110") (pintype "bidirectional+no_connect"))
    )
    (net (code "123") (name "unconnected-(U1A-I{slash}O-Pad127)") (class "Default")
      (node (ref "U1") (pin "127") (pinfunction "I/O_127") (pintype "bidirectional+no_connect"))
    )
    (net (code "124") (name "unconnected-(U1A-I{slash}O-Pad134)") (class "Default")
      (node (ref "U1") (pin "134") (pinfunction "I/O_134") (pintype "bidirectional+no_connect"))
    )
    (net (code "125") (name "unconnected-(U1A-I{slash}O-Pad147)") (class "Default")
      (node (ref "U1") (pin "147") (pinfunction "I/O_147") (pintype "bidirectional+no_connect"))
    )
    (net (code "126") (name "unconnected-(U1A-I{slash}O-Pad148)") (class "Default")
      (node (ref "U1") (pin "148") (pinfunction "I/O_148") (pintype "bidirectional+no_connect"))
    )
    (net (code "127") (name "unconnected-(U1A-I{slash}O-Pad149)") (class "Default")
      (node (ref "U1") (pin "149") (pinfunction "I/O_149") (pintype "bidirectional+no_connect"))
    )
    (net (code "128") (name "unconnected-(U1A-I{slash}O-Pad163)") (class "Default")
      (node (ref "U1") (pin "163") (pinfunction "I/O_163") (pintype "bidirectional+no_connect"))
    )
    (net (code "129") (name "unconnected-(U1A-I{slash}O-Pad166)") (class "Default")
      (node (ref "U1") (pin "166") (pinfunction "I/O_166") (pintype "bidirectional+no_connect"))
    )
    (net (code "130") (name "unconnected-(U1A-I{slash}O-Pad167)") (class "Default")
      (node (ref "U1") (pin "167") (pinfunction "I/O_167") (pintype "bidirectional+no_connect"))
    )
    (net (code "131") (name "unconnected-(U1A-I{slash}O-Pad180)") (class "Default")
      (node (ref "U1") (pin "180") (pinfunction "I/O_180") (pintype "bidirectional+no_connect"))
    )
    (net (code "132") (name "unconnected-(U1A-I{slash}O-Pad200)") (class "Default")
      (node (ref "U1") (pin "200") (pinfunction "I/O_200") (pintype "bidirectional+no_connect"))
    )
    (net (code "133") (name "unconnected-(U1A-I{slash}O-Pad201)") (class "Default")
      (node (ref "U1") (pin "201") (pinfunction "I/O_201") (pintype "bidirectional+no_connect"))
    )
    (net (code "134") (name "unconnected-(U1A-I{slash}O-Pad204)") (class "Default")
      (node (ref "U1") (pin "204") (pinfunction "I/O_204") (pintype "bidirectional+no_connect"))
    )
    (net (code "135") (name "unconnected-(U1A-I{slash}O-Pad206)") (class "Default")
      (node (ref "U1") (pin "206") (pinfunction "I/O_206") (pintype "bidirectional+no_connect"))
    )
    (net (code "136") (name "unconnected-(U1A-I{slash}O_(D2),_L15P_YY-Pad141)") (class "Default")
      (node (ref "U1") (pin "141") (pinfunction "I/O_(D2),_L15P_YY_141") (pintype "bidirectional+no_connect"))
    )
    (net (code "137") (name "unconnected-(U1A-I{slash}O_(D3),_L17N-Pad135)") (class "Default")
      (node (ref "U1") (pin "135") (pinfunction "I/O_(D3),_L17N_135") (pintype "bidirectional+no_connect"))
    )
    (net (code "138") (name "unconnected-(U1A-I{slash}O_(D4),_L19P-Pad126)") (class "Default")
      (node (ref "U1") (pin "126") (pinfunction "I/O_(D4),_L19P_126") (pintype "bidirectional+no_connect"))
    )
    (net (code "139") (name "unconnected-(U1A-I{slash}O_(D5),_L21N_YY-Pad120)") (class "Default")
      (node (ref "U1") (pin "120") (pinfunction "I/O_(D5),_L21N_YY_120") (pintype "bidirectional+no_connect"))
    )
    (net (code "140") (name "unconnected-(U1A-I{slash}O_(D7),_L24P_YY-Pad108)") (class "Default")
      (node (ref "U1") (pin "108") (pinfunction "I/O_(D7),_L24P_YY_108") (pintype "bidirectional+no_connect"))
    )
    (net (code "141") (name "unconnected-(U1A-I{slash}O_(DLL),_L5N-Pad187)") (class "Default")
      (node (ref "U1") (pin "187") (pinfunction "I/O_(DLL),_L5N_187") (pintype "bidirectional+no_connect"))
    )
    (net (code "142") (name "unconnected-(U1A-I{slash}O_(DLL),_L5P-Pad181)") (class "Default")
      (node (ref "U1") (pin "181") (pinfunction "I/O_(DLL),_L5P_181") (pintype "bidirectional+no_connect"))
    )
    (net (code "143") (name "unconnected-(U1A-I{slash}O_(DLL),_L31N-Pad75)") (class "Default")
      (node (ref "U1") (pin "75") (pinfunction "I/O_(DLL),_L31N_75") (pintype "bidirectional+no_connect"))
    )
    (net (code "144") (name "unconnected-(U1A-I{slash}O_(DLL),_L31P-Pad81)") (class "Default")
      (node (ref "U1") (pin "81") (pinfunction "I/O_(DLL),_L31P_81") (pintype "bidirectional+no_connect"))
    )
    (net (code "145") (name "unconnected-(U1A-I{slash}O_(DOUT,_BUSY),_L12P_YY-Pad154)") (class "Default")
      (node (ref "U1") (pin "154") (pinfunction "I/O_(DOUT,_BUSY),_L12P_YY_154") (pintype "bidirectional+no_connect"))
    )
    (net (code "146") (name "unconnected-(U1A-I{slash}O_(IRDY),_L18N_YY-Pad132)") (class "Default")
      (node (ref "U1") (pin "132") (pinfunction "I/O_(IRDY),_L18N_YY_132") (pintype "bidirectional+no_connect"))
    )
    (net (code "147") (name "unconnected-(U1A-I{slash}O_(IRDY),_L44N_YY-Pad24)") (class "Default")
      (node (ref "U1") (pin "24") (pinfunction "I/O_(IRDY),_L44N_YY_24") (pintype "bidirectional+no_connect"))
    )
    (net (code "148") (name "unconnected-(U1A-I{slash}O_(TRDY)-Pad27)") (class "Default")
      (node (ref "U1") (pin "27") (pinfunction "I/O_(TRDY)_27") (pintype "bidirectional+no_connect"))
    )
    (net (code "149") (name "unconnected-(U1A-I{slash}O_(TRDY)-Pad129)") (class "Default")
      (node (ref "U1") (pin "129") (pinfunction "I/O_(TRDY)_129") (pintype "bidirectional+no_connect"))
    )
    (net (code "150") (name "unconnected-(U1A-I{slash}O_(~{CS}),_L11P_YY-Pad160)") (class "Default")
      (node (ref "U1") (pin "160") (pinfunction "I/O_(~{CS}),_L11P_YY_160") (pintype "bidirectional+no_connect"))
    )
    (net (code "151") (name "unconnected-(U1A-I{slash}O_(~{WRITE}),_L11N_YY-Pad161)") (class "Default")
      (node (ref "U1") (pin "161") (pinfunction "I/O_(~{WRITE}),_L11N_YY_161") (pintype "bidirectional+no_connect"))
    )
    (net (code "152") (name "unconnected-(U2A-GCK0,_I-Pad80)") (class "Default")
      (node (ref "U2") (pin "80") (pinfunction "GCK0,_I_80") (pintype "input+no_connect"))
    )
    (net (code "153") (name "unconnected-(U2A-GCK1,_I-Pad77)") (class "Default")
      (node (ref "U2") (pin "77") (pinfunction "GCK1,_I_77") (pintype "input+no_connect"))
    )
    (net (code "154") (name "unconnected-(U2A-GCK2,_I-Pad182)") (class "Default")
      (node (ref "U2") (pin "182") (pinfunction "GCK2,_I_182") (pintype "input+no_connect"))
    )
    (net (code "155") (name "unconnected-(U2A-GCK3,_I-Pad185)") (class "Default")
      (node (ref "U2") (pin "185") (pinfunction "GCK3,_I_185") (pintype "input+no_connect"))
    )
    (net (code "156") (name "unconnected-(U2A-I{slash}O,_L0P_YY-Pad202)") (class "Default")
      (node (ref "U2") (pin "202") (pinfunction "I/O,_L0P_YY_202") (pintype "bidirectional+no_connect"))
    )
    (net (code "157") (name "unconnected-(U2A-I{slash}O,_L1P_Y-Pad198)") (class "Default")
      (node (ref "U2") (pin "198") (pinfunction "I/O,_L1P_Y_198") (pintype "bidirectional+no_connect"))
    )
    (net (code "158") (name "unconnected-(U2A-I{slash}O,_L2N_Y-Pad194)") (class "Default")
      (node (ref "U2") (pin "194") (pinfunction "I/O,_L2N_Y_194") (pintype "bidirectional+no_connect"))
    )
    (net (code "159") (name "unconnected-(U2A-I{slash}O,_L2P_Y-Pad193)") (class "Default")
      (node (ref "U2") (pin "193") (pinfunction "I/O,_L2P_Y_193") (pintype "bidirectional+no_connect"))
    )
    (net (code "160") (name "unconnected-(U2A-I{slash}O,_L3N_Y-Pad192)") (class "Default")
      (node (ref "U2") (pin "192") (pinfunction "I/O,_L3N_Y_192") (pintype "bidirectional+no_connect"))
    )
    (net (code "161") (name "unconnected-(U2A-I{slash}O,_L3P_Y-Pad191)") (class "Default")
      (node (ref "U2") (pin "191") (pinfunction "I/O,_L3P_Y_191") (pintype "bidirectional+no_connect"))
    )
    (net (code "162") (name "unconnected-(U2A-I{slash}O,_L4P_Y-Pad188)") (class "Default")
      (node (ref "U2") (pin "188") (pinfunction "I/O,_L4P_Y_188") (pintype "bidirectional+no_connect"))
    )
    (net (code "163") (name "unconnected-(U2A-I{slash}O,_L6N_Y-Pad179)") (class "Default")
      (node (ref "U2") (pin "179") (pinfunction "I/O,_L6N_Y_179") (pintype "bidirectional+no_connect"))
    )
    (net (code "164") (name "unconnected-(U2A-I{slash}O,_L7N_Y-Pad176)") (class "Default")
      (node (ref "U2") (pin "176") (pinfunction "I/O,_L7N_Y_176") (pintype "bidirectional+no_connect"))
    )
    (net (code "165") (name "unconnected-(U2A-I{slash}O,_L7P_Y-Pad175)") (class "Default")
      (node (ref "U2") (pin "175") (pinfunction "I/O,_L7P_Y_175") (pintype "bidirectional+no_connect"))
    )
    (net (code "166") (name "unconnected-(U2A-I{slash}O,_L8N_Y-Pad174)") (class "Default")
      (node (ref "U2") (pin "174") (pinfunction "I/O,_L8N_Y_174") (pintype "bidirectional+no_connect"))
    )
    (net (code "167") (name "unconnected-(U2A-I{slash}O,_L8P_Y-Pad173)") (class "Default")
      (node (ref "U2") (pin "173") (pinfunction "I/O,_L8P_Y_173") (pintype "bidirectional+no_connect"))
    )
    (net (code "168") (name "unconnected-(U2A-I{slash}O,_L9N_Y-Pad169)") (class "Default")
      (node (ref "U2") (pin "169") (pinfunction "I/O,_L9N_Y_169") (pintype "bidirectional+no_connect"))
    )
    (net (code "169") (name "unconnected-(U2A-I{slash}O,_L10N_YY-Pad165)") (class "Default")
      (node (ref "U2") (pin "165") (pinfunction "I/O,_L10N_YY_165") (pintype "bidirectional+no_connect"))
    )
    (net (code "170") (name "unconnected-(U2A-I{slash}O,_L13P-Pad151)") (class "Default")
      (node (ref "U2") (pin "151") (pinfunction "I/O,_L13P_151") (pintype "bidirectional+no_connect"))
    )
    (net (code "171") (name "unconnected-(U2A-I{slash}O,_L15N_YY-Pad140)") (class "Default")
      (node (ref "U2") (pin "140") (pinfunction "I/O,_L15N_YY_140") (pintype "bidirectional+no_connect"))
    )
    (net (code "172") (name "unconnected-(U2A-I{slash}O,_L16N_YY-Pad138)") (class "Default")
      (node (ref "U2") (pin "138") (pinfunction "I/O,_L16N_YY_138") (pintype "bidirectional+no_connect"))
    )
    (net (code "173") (name "unconnected-(U2A-I{slash}O,_L16P_YY-Pad139)") (class "Default")
      (node (ref "U2") (pin "139") (pinfunction "I/O,_L16P_YY_139") (pintype "bidirectional+no_connect"))
    )
    (net (code "174") (name "unconnected-(U2A-I{slash}O,_L18P_YY-Pad133)") (class "Default")
      (node (ref "U2") (pin "133") (pinfunction "I/O,_L18P_YY_133") (pintype "bidirectional+no_connect"))
    )
    (net (code "175") (name "unconnected-(U2A-I{slash}O,_L20N_YY-Pad122)") (class "Default")
      (node (ref "U2") (pin "122") (pinfunction "I/O,_L20N_YY_122") (pintype "bidirectional+no_connect"))
    )
    (net (code "176") (name "unconnected-(U2A-I{slash}O,_L20P_YY-Pad123)") (class "Default")
      (node (ref "U2") (pin "123") (pinfunction "I/O,_L20P_YY_123") (pintype "bidirectional+no_connect"))
    )
    (net (code "177") (name "unconnected-(U2A-I{slash}O,_L21P_YY-Pad121)") (class "Default")
      (node (ref "U2") (pin "121") (pinfunction "I/O,_L21P_YY_121") (pintype "bidirectional+no_connect"))
    )
    (net (code "178") (name "unconnected-(U2A-I{slash}O,_L23P_Y-Pad112)") (class "Default")
      (node (ref "U2") (pin "112") (pinfunction "I/O,_L23P_Y_112") (pintype "bidirectional+no_connect"))
    )
    (net (code "179") (name "unconnected-(U2A-I{slash}O,_L25N_YY-Pad101)") (class "Default")
      (node (ref "U2") (pin "101") (pinfunction "I/O,_L25N_YY_101") (pintype "bidirectional+no_connect"))
    )
    (net (code "180") (name "unconnected-(U2A-I{slash}O,_L25P_YY-Pad102)") (class "Default")
      (node (ref "U2") (pin "102") (pinfunction "I/O,_L25P_YY_102") (pintype "bidirectional+no_connect"))
    )
    (net (code "181") (name "unconnected-(U2A-I{slash}O,_L26N_YY-Pad97)") (class "Default")
      (node (ref "U2") (pin "97") (pinfunction "I/O,_L26N_YY_97") (pintype "bidirectional+no_connect"))
    )
    (net (code "182") (name "unconnected-(U2A-I{slash}O,_L27N_Y-Pad93)") (class "Default")
      (node (ref "U2") (pin "93") (pinfunction "I/O,_L27N_Y_93") (pintype "bidirectional+no_connect"))
    )
    (net (code "183") (name "unconnected-(U2A-I{slash}O,_L28N_Y-Pad88)") (class "Default")
      (node (ref "U2") (pin "88") (pinfunction "I/O,_L28N_Y_88") (pintype "bidirectional+no_connect"))
    )
    (net (code "184") (name "unconnected-(U2A-I{slash}O,_L28P_Y-Pad89)") (class "Default")
      (node (ref "U2") (pin "89") (pinfunction "I/O,_L28P_Y_89") (pintype "bidirectional+no_connect"))
    )
    (net (code "185") (name "unconnected-(U2A-I{slash}O,_L29N_Y-Pad86)") (class "Default")
      (node (ref "U2") (pin "86") (pinfunction "I/O,_L29N_Y_86") (pintype "bidirectional+no_connect"))
    )
    (net (code "186") (name "unconnected-(U2A-I{slash}O,_L29P_Y-Pad87)") (class "Default")
      (node (ref "U2") (pin "87") (pinfunction "I/O,_L29P_Y_87") (pintype "bidirectional+no_connect"))
    )
    (net (code "187") (name "unconnected-(U2A-I{slash}O,_L30N_Y-Pad83)") (class "Default")
      (node (ref "U2") (pin "83") (pinfunction "I/O,_L30N_Y_83") (pintype "bidirectional+no_connect"))
    )
    (net (code "188") (name "unconnected-(U2A-I{slash}O,_L32N-Pad71)") (class "Default")
      (node (ref "U2") (pin "71") (pinfunction "I/O,_L32N_71") (pintype "bidirectional+no_connect"))
    )
    (net (code "189") (name "unconnected-(U2A-I{slash}O,_L33N_Y-Pad68)") (class "Default")
      (node (ref "U2") (pin "68") (pinfunction "I/O,_L33N_Y_68") (pintype "bidirectional+no_connect"))
    )
    (net (code "190") (name "unconnected-(U2A-I{slash}O,_L33P_Y-Pad69)") (class "Default")
      (node (ref "U2") (pin "69") (pinfunction "I/O,_L33P_Y_69") (pintype "bidirectional+no_connect"))
    )
    (net (code "191") (name "unconnected-(U2A-I{slash}O,_L34P_Y-Pad64)") (class "Default")
      (node (ref "U2") (pin "64") (pinfunction "I/O,_L34P_Y_64") (pintype "bidirectional+no_connect"))
    )
    (net (code "192") (name "unconnected-(U2A-I{slash}O,_L35N-Pad61)") (class "Default")
      (node (ref "U2") (pin "61") (pinfunction "I/O,_L35N_61") (pintype "bidirectional+no_connect"))
    )
    (net (code "193") (name "unconnected-(U2A-I{slash}O,_L35P-Pad62)") (class "Default")
      (node (ref "U2") (pin "62") (pinfunction "I/O,_L35P_62") (pintype "bidirectional+no_connect"))
    )
    (net (code "194") (name "unconnected-(U2A-I{slash}O,_L36P_YY-Pad60)") (class "Default")
      (node (ref "U2") (pin "60") (pinfunction "I/O,_L36P_YY_60") (pintype "bidirectional+no_connect"))
    )
    (net (code "195") (name "unconnected-(U2A-I{slash}O,_L37N_YY-Pad55)") (class "Default")
      (node (ref "U2") (pin "55") (pinfunction "I/O,_L37N_YY_55") (pintype "bidirectional+no_connect"))
    )
    (net (code "196") (name "unconnected-(U2A-I{slash}O,_L37P_YY-Pad56)") (class "Default")
      (node (ref "U2") (pin "56") (pinfunction "I/O,_L37P_YY_56") (pintype "bidirectional+no_connect"))
    )
    (net (code "197") (name "unconnected-(U2A-I{slash}O,_L38N_YY-Pad49)") (class "Default")
      (node (ref "U2") (pin "49") (pinfunction "I/O,_L38N_YY_49") (pintype "bidirectional+no_connect"))
    )
    (net (code "198") (name "unconnected-(U2A-I{slash}O,_L38P_YY-Pad48)") (class "Default")
      (node (ref "U2") (pin "48") (pinfunction "I/O,_L38P_YY_48") (pintype "bidirectional+no_connect"))
    )
    (net (code "199") (name "unconnected-(U2A-I{slash}O,_L40P-Pad40)") (class "Default")
      (node (ref "U2") (pin "40") (pinfunction "I/O,_L40P_40") (pintype "bidirectional+no_connect"))
    )
    (net (code "200") (name "unconnected-(U2A-I{slash}O,_L41N_YY-Pad36)") (class "Default")
      (node (ref "U2") (pin "36") (pinfunction "I/O,_L41N_YY_36") (pintype "bidirectional+no_connect"))
    )
    (net (code "201") (name "unconnected-(U2A-I{slash}O,_L41P_YY-Pad35)") (class "Default")
      (node (ref "U2") (pin "35") (pinfunction "I/O,_L41P_YY_35") (pintype "bidirectional+no_connect"))
    )
    (net (code "202") (name "unconnected-(U2A-I{slash}O,_L43P-Pad30)") (class "Default")
      (node (ref "U2") (pin "30") (pinfunction "I/O,_L43P_30") (pintype "bidirectional+no_connect"))
    )
    (net (code "203") (name "unconnected-(U2A-I{slash}O,_L44P_YY-Pad23)") (class "Default")
      (node (ref "U2") (pin "23") (pinfunction "I/O,_L44P_YY_23") (pintype "bidirectional+no_connect"))
    )
    (net (code "204") (name "unconnected-(U2A-I{slash}O,_L45N-Pad21)") (class "Default")
      (node (ref "U2") (pin "21") (pinfunction "I/O,_L45N_21") (pintype "bidirectional+no_connect"))
    )
    (net (code "205") (name "unconnected-(U2A-I{slash}O,_L46N_YY-Pad18)") (class "Default")
      (node (ref "U2") (pin "18") (pinfunction "I/O,_L46N_YY_18") (pintype "bidirectional+no_connect"))
    )
    (net (code "206") (name "unconnected-(U2A-I{slash}O,_L46P_YY-Pad17)") (class "Default")
      (node (ref "U2") (pin "17") (pinfunction "I/O,_L46P_YY_17") (pintype "bidirectional+no_connect"))
    )
    (net (code "207") (name "unconnected-(U2A-I{slash}O,_L47N_YY-Pad16)") (class "Default")
      (node (ref "U2") (pin "16") (pinfunction "I/O,_L47N_YY_16") (pintype "bidirectional+no_connect"))
    )
    (net (code "208") (name "unconnected-(U2A-I{slash}O,_L47P_YY-Pad15)") (class "Default")
      (node (ref "U2") (pin "15") (pinfunction "I/O,_L47P_YY_15") (pintype "bidirectional+no_connect"))
    )
    (net (code "209") (name "unconnected-(U2A-I{slash}O,_L49N_Y-Pad7)") (class "Default")
      (node (ref "U2") (pin "7") (pinfunction "I/O,_L49N_Y_7") (pintype "bidirectional+no_connect"))
    )
    (net (code "210") (name "unconnected-(U2A-I{slash}O,_VREF_0,_L0N_YY-Pad203)") (class "Default")
      (node (ref "U2") (pin "203") (pinfunction "I/O,_VREF_0,_L0N_YY_203") (pintype "bidirectional+no_connect"))
    )
    (net (code "211") (name "unconnected-(U2A-I{slash}O,_VREF_0,_L1N_Y-Pad199)") (class "Default")
      (node (ref "U2") (pin "199") (pinfunction "I/O,_VREF_0,_L1N_Y_199") (pintype "bidirectional+no_connect"))
    )
    (net (code "212") (name "unconnected-(U2A-I{slash}O,_VREF_0,_L4N_Y-Pad189)") (class "Default")
      (node (ref "U2") (pin "189") (pinfunction "I/O,_VREF_0,_L4N_Y_189") (pintype "bidirectional+no_connect"))
    )
    (net (code "213") (name "unconnected-(U2A-I{slash}O,_VREF_0-Pad205)") (class "Default")
      (node (ref "U2") (pin "205") (pinfunction "I/O,_VREF_0_205") (pintype "bidirectional+no_connect"))
    )
    (net (code "214") (name "unconnected-(U2A-I{slash}O,_VREF_1,_L6P_Y-Pad178)") (class "Default")
      (node (ref "U2") (pin "178") (pinfunction "I/O,_VREF_1,_L6P_Y_178") (pintype "bidirectional+no_connect"))
    )
    (net (code "215") (name "unconnected-(U2A-I{slash}O,_VREF_1,_L9P_Y-Pad168)") (class "Default")
      (node (ref "U2") (pin "168") (pinfunction "I/O,_VREF_1,_L9P_Y_168") (pintype "bidirectional+no_connect"))
    )
    (net (code "216") (name "unconnected-(U2A-I{slash}O,_VREF_1,_L10P_YY-Pad164)") (class "Default")
      (node (ref "U2") (pin "164") (pinfunction "I/O,_VREF_1,_L10P_YY_164") (pintype "bidirectional+no_connect"))
    )
    (net (code "217") (name "unconnected-(U2A-I{slash}O,_VREF_1-Pad162)") (class "Default")
      (node (ref "U2") (pin "162") (pinfunction "I/O,_VREF_1_162") (pintype "bidirectional+no_connect"))
    )
    (net (code "218") (name "unconnected-(U2A-I{slash}O,_VREF_2,_L13N-Pad150)") (class "Default")
      (node (ref "U2") (pin "150") (pinfunction "I/O,_VREF_2,_L13N_150") (pintype "bidirectional+no_connect"))
    )
    (net (code "219") (name "unconnected-(U2A-I{slash}O,_VREF_2,_L14P-Pad146)") (class "Default")
      (node (ref "U2") (pin "146") (pinfunction "I/O,_VREF_2,_L14P_146") (pintype "bidirectional+no_connect"))
    )
    (net (code "220") (name "unconnected-(U2A-I{slash}O,_VREF_2,_L17P-Pad136)") (class "Default")
      (node (ref "U2") (pin "136") (pinfunction "I/O,_VREF_2,_L17P_136") (pintype "bidirectional+no_connect"))
    )
    (net (code "221") (name "unconnected-(U2A-I{slash}O,_VREF_2-Pad152)") (class "Default")
      (node (ref "U2") (pin "152") (pinfunction "I/O,_VREF_2_152") (pintype "bidirectional+no_connect"))
    )
    (net (code "222") (name "unconnected-(U2A-I{slash}O,_VREF_3,_L19N-Pad125)") (class "Default")
      (node (ref "U2") (pin "125") (pinfunction "I/O,_VREF_3,_L19N_125") (pintype "bidirectional+no_connect"))
    )
    (net (code "223") (name "unconnected-(U2A-I{slash}O,_VREF_3,_L22N-Pad115)") (class "Default")
      (node (ref "U2") (pin "115") (pinfunction "I/O,_VREF_3,_L22N_115") (pintype "bidirectional+no_connect"))
    )
    (net (code "224") (name "unconnected-(U2A-I{slash}O,_VREF_3,_L23N_Y-Pad111)") (class "Default")
      (node (ref "U2") (pin "111") (pinfunction "I/O,_VREF_3,_L23N_Y_111") (pintype "bidirectional+no_connect"))
    )
    (net (code "225") (name "unconnected-(U2A-I{slash}O,_VREF_3-Pad109)") (class "Default")
      (node (ref "U2") (pin "109") (pinfunction "I/O,_VREF_3_109") (pintype "bidirectional+no_connect"))
    )
    (net (code "226") (name "unconnected-(U2A-I{slash}O,_VREF_4,_L26P_YY-Pad98)") (class "Default")
      (node (ref "U2") (pin "98") (pinfunction "I/O,_VREF_4,_L26P_YY_98") (pintype "bidirectional+no_connect"))
    )
    (net (code "227") (name "unconnected-(U2A-I{slash}O,_VREF_4,_L27P_Y-Pad94)") (class "Default")
      (node (ref "U2") (pin "94") (pinfunction "I/O,_VREF_4,_L27P_Y_94") (pintype "bidirectional+no_connect"))
    )
    (net (code "228") (name "unconnected-(U2A-I{slash}O,_VREF_4,_L30P_Y-Pad84)") (class "Default")
      (node (ref "U2") (pin "84") (pinfunction "I/O,_VREF_4,_L30P_Y_84") (pintype "bidirectional+no_connect"))
    )
    (net (code "229") (name "unconnected-(U2A-I{slash}O,_VREF_4-Pad100)") (class "Default")
      (node (ref "U2") (pin "100") (pinfunction "I/O,_VREF_4_100") (pintype "bidirectional+no_connect"))
    )
    (net (code "230") (name "unconnected-(U2A-I{slash}O,_VREF_5,_L32P-Pad73)") (class "Default")
      (node (ref "U2") (pin "73") (pinfunction "I/O,_VREF_5,_L32P_73") (pintype "bidirectional+no_connect"))
    )
    (net (code "231") (name "unconnected-(U2A-I{slash}O,_VREF_5,_L34N_Y-Pad63)") (class "Default")
      (node (ref "U2") (pin "63") (pinfunction "I/O,_VREF_5,_L34N_Y_63") (pintype "bidirectional+no_connect"))
    )
    (net (code "232") (name "unconnected-(U2A-I{slash}O,_VREF_5,_L36N_YY-Pad59)") (class "Default")
      (node (ref "U2") (pin "59") (pinfunction "I/O,_VREF_5,_L36N_YY_59") (pintype "bidirectional+no_connect"))
    )
    (net (code "233") (name "unconnected-(U2A-I{slash}O,_VREF_5-Pad57)") (class "Default")
      (node (ref "U2") (pin "57") (pinfunction "I/O,_VREF_5_57") (pintype "bidirectional+no_connect"))
    )
    (net (code "234") (name "unconnected-(U2A-I{slash}O,_VREF_6,_L43N-Pad31)") (class "Default")
      (node (ref "U2") (pin "31") (pinfunction "I/O,_VREF_6,_L43N_31") (pintype "bidirectional+no_connect"))
    )
    (net (code "235") (name "unconnected-(U2A-I{slash}O,_VREF_6-Pad47)") (class "Default")
      (node (ref "U2") (pin "47") (pinfunction "I/O,_VREF_6_47") (pintype "bidirectional+no_connect"))
    )
    (net (code "236") (name "unconnected-(U2A-I{slash}O,_VREF_7,_L45P-Pad20)") (class "Default")
      (node (ref "U2") (pin "20") (pinfunction "I/O,_VREF_7,_L45P_20") (pintype "bidirectional+no_connect"))
    )
    (net (code "237") (name "unconnected-(U2A-I{slash}O,_VREF_7,_L49P_Y-Pad6)") (class "Default")
      (node (ref "U2") (pin "6") (pinfunction "I/O,_VREF_7,_L49P_Y_6") (pintype "bidirectional+no_connect"))
    )
    (net (code "238") (name "unconnected-(U2A-I{slash}O,_VREF_7-Pad4)") (class "Default")
      (node (ref "U2") (pin "4") (pinfunction "I/O,_VREF_7_4") (pintype "bidirectional+no_connect"))
    )
    (net (code "239") (name "unconnected-(U2A-I{slash}O-Pad3)") (class "Default")
      (node (ref "U2") (pin "3") (pinfunction "I/O_3") (pintype "bidirectional+no_connect"))
    )
    (net (code "240") (name "unconnected-(U2A-I{slash}O-Pad5)") (class "Default")
      (node (ref "U2") (pin "5") (pinfunction "I/O_5") (pintype "bidirectional+no_connect"))
    )
    (net (code "241") (name "unconnected-(U2A-I{slash}O-Pad8)") (class "Default")
      (node (ref "U2") (pin "8") (pinfunction "I/O_8") (pintype "bidirectional+no_connect"))
    )
    (net (code "242") (name "unconnected-(U2A-I{slash}O-Pad9)") (class "Default")
      (node (ref "U2") (pin "9") (pinfunction "I/O_9") (pintype "bidirectional+no_connect"))
    )
    (net (code "243") (name "unconnected-(U2A-I{slash}O-Pad22)") (class "Default")
      (node (ref "U2") (pin "22") (pinfunction "I/O_22") (pintype "bidirectional+no_connect"))
    )
    (net (code "244") (name "unconnected-(U2A-I{slash}O-Pad29)") (class "Default")
      (node (ref "U2") (pin "29") (pinfunction "I/O_29") (pintype "bidirectional+no_connect"))
    )
    (net (code "245") (name "unconnected-(U2A-I{slash}O-Pad58)") (class "Default")
      (node (ref "U2") (pin "58") (pinfunction "I/O_58") (pintype "bidirectional+no_connect"))
    )
    (net (code "246") (name "unconnected-(U2A-I{slash}O-Pad70)") (class "Default")
      (node (ref "U2") (pin "70") (pinfunction "I/O_70") (pintype "bidirectional+no_connect"))
    )
    (net (code "247") (name "unconnected-(U2A-I{slash}O-Pad74)") (class "Default")
      (node (ref "U2") (pin "74") (pinfunction "I/O_74") (pintype "bidirectional+no_connect"))
    )
    (net (code "248") (name "unconnected-(U2A-I{slash}O-Pad82)") (class "Default")
      (node (ref "U2") (pin "82") (pinfunction "I/O_82") (pintype "bidirectional+no_connect"))
    )
    (net (code "249") (name "unconnected-(U2A-I{slash}O-Pad95)") (class "Default")
      (node (ref "U2") (pin "95") (pinfunction "I/O_95") (pintype "bidirectional+no_connect"))
    )
    (net (code "250") (name "unconnected-(U2A-I{slash}O-Pad96)") (class "Default")
      (node (ref "U2") (pin "96") (pinfunction "I/O_96") (pintype "bidirectional+no_connect"))
    )
    (net (code "251") (name "unconnected-(U2A-I{slash}O-Pad99)") (class "Default")
      (node (ref "U2") (pin "99") (pinfunction "I/O_99") (pintype "bidirectional+no_connect"))
    )
    (net (code "252") (name "unconnected-(U2A-I{slash}O-Pad110)") (class "Default")
      (node (ref "U2") (pin "110") (pinfunction "I/O_110") (pintype "bidirectional+no_connect"))
    )
    (net (code "253") (name "unconnected-(U2A-I{slash}O-Pad113)") (class "Default")
      (node (ref "U2") (pin "113") (pinfunction "I/O_113") (pintype "bidirectional+no_connect"))
    )
    (net (code "254") (name "unconnected-(U2A-I{slash}O-Pad114)") (class "Default")
      (node (ref "U2") (pin "114") (pinfunction "I/O_114") (pintype "bidirectional+no_connect"))
    )
    (net (code "255") (name "unconnected-(U2A-I{slash}O-Pad127)") (class "Default")
      (node (ref "U2") (pin "127") (pinfunction "I/O_127") (pintype "bidirectional+no_connect"))
    )
    (net (code "256") (name "unconnected-(U2A-I{slash}O-Pad134)") (class "Default")
      (node (ref "U2") (pin "134") (pinfunction "I/O_134") (pintype "bidirectional+no_connect"))
    )
    (net (code "257") (name "unconnected-(U2A-I{slash}O-Pad147)") (class "Default")
      (node (ref "U2") (pin "147") (pinfunction "I/O_147") (pintype "bidirectional+no_connect"))
    )
    (net (code "258") (name "unconnected-(U2A-I{slash}O-Pad148)") (class "Default")
      (node (ref "U2") (pin "148") (pinfunction "I/O_148") (pintype "bidirectional+no_connect"))
    )
    (net (code "259") (name "unconnected-(U2A-I{slash}O-Pad149)") (class "Default")
      (node (ref "U2") (pin "149") (pinfunction "I/O_149") (pintype "bidirectional+no_connect"))
    )
    (net (code "260") (name "unconnected-(U2A-I{slash}O-Pad163)") (class "Default")
      (node (ref "U2") (pin "163") (pinfunction "I/O_163") (pintype "bidirectional+no_connect"))
    )
    (net (code "261") (name "unconnected-(U2A-I{slash}O-Pad166)") (class "Default")
      (node (ref "U2") (pin "166") (pinfunction "I/O_166") (pintype "bidirectional+no_connect"))
    )
    (net (code "262") (name "unconnected-(U2A-I{slash}O-Pad167)") (class "Default")
      (node (ref "U2") (pin "167") (pinfunction "I/O_167") (pintype "bidirectional+no_connect"))
    )
    (net (code "263") (name "unconnected-(U2A-I{slash}O-Pad180)") (class "Default")
      (node (ref "U2") (pin "180") (pinfunction "I/O_180") (pintype "bidirectional+no_connect"))
    )
    (net (code "264") (name "unconnected-(U2A-I{slash}O-Pad200)") (class "Default")
      (node (ref "U2") (pin "200") (pinfunction "I/O_200") (pintype "bidirectional+no_connect"))
    )
    (net (code "265") (name "unconnected-(U2A-I{slash}O-Pad201)") (class "Default")
      (node (ref "U2") (pin "201") (pinfunction "I/O_201") (pintype "bidirectional+no_connect"))
    )
    (net (code "266") (name "unconnected-(U2A-I{slash}O-Pad204)") (class "Default")
      (node (ref "U2") (pin "204") (pinfunction "I/O_204") (pintype "bidirectional+no_connect"))
    )
    (net (code "267") (name "unconnected-(U2A-I{slash}O-Pad206)") (class "Default")
      (node (ref "U2") (pin "206") (pinfunction "I/O_206") (pintype "bidirectional+no_connect"))
    )
    (net (code "268") (name "unconnected-(U2A-I{slash}O_(D1),_L14N-Pad145)") (class "Default")
      (node (ref "U2") (pin "145") (pinfunction "I/O_(D1),_L14N_145") (pintype "bidirectional+no_connect"))
    )
    (net (code "269") (name "unconnected-(U2A-I{slash}O_(D2),_L15P_YY-Pad141)") (class "Default")
      (node (ref "U2") (pin "141") (pinfunction "I/O_(D2),_L15P_YY_141") (pintype "bidirectional+no_connect"))
    )
    (net (code "270") (name "unconnected-(U2A-I{slash}O_(D3),_L17N-Pad135)") (class "Default")
      (node (ref "U2") (pin "135") (pinfunction "I/O_(D3),_L17N_135") (pintype "bidirectional+no_connect"))
    )
    (net (code "271") (name "unconnected-(U2A-I{slash}O_(D4),_L19P-Pad126)") (class "Default")
      (node (ref "U2") (pin "126") (pinfunction "I/O_(D4),_L19P_126") (pintype "bidirectional+no_connect"))
    )
    (net (code "272") (name "unconnected-(U2A-I{slash}O_(D5),_L21N_YY-Pad120)") (class "Default")
      (node (ref "U2") (pin "120") (pinfunction "I/O_(D5),_L21N_YY_120") (pintype "bidirectional+no_connect"))
    )
    (net (code "273") (name "unconnected-(U2A-I{slash}O_(D6),_L22P-Pad116)") (class "Default")
      (node (ref "U2") (pin "116") (pinfunction "I/O_(D6),_L22P_116") (pintype "bidirectional"))
    )
    (net (code "274") (name "unconnected-(U2A-I{slash}O_(D7),_L24P_YY-Pad108)") (class "Default")
      (node (ref "U2") (pin "108") (pinfunction "I/O_(D7),_L24P_YY_108") (pintype "bidirectional+no_connect"))
    )
    (net (code "275") (name "unconnected-(U2A-I{slash}O_(DLL),_L5N-Pad187)") (class "Default")
      (node (ref "U2") (pin "187") (pinfunction "I/O_(DLL),_L5N_187") (pintype "bidirectional+no_connect"))
    )
    (net (code "276") (name "unconnected-(U2A-I{slash}O_(DLL),_L5P-Pad181)") (class "Default")
      (node (ref "U2") (pin "181") (pinfunction "I/O_(DLL),_L5P_181") (pintype "bidirectional+no_connect"))
    )
    (net (code "277") (name "unconnected-(U2A-I{slash}O_(DLL),_L31N-Pad75)") (class "Default")
      (node (ref "U2") (pin "75") (pinfunction "I/O_(DLL),_L31N_75") (pintype "bidirectional+no_connect"))
    )
    (net (code "278") (name "unconnected-(U2A-I{slash}O_(DLL),_L31P-Pad81)") (class "Default")
      (node (ref "U2") (pin "81") (pinfunction "I/O_(DLL),_L31P_81") (pintype "bidirectional+no_connect"))
    )
    (net (code "279") (name "unconnected-(U2A-I{slash}O_(DOUT,_BUSY),_L12P_YY-Pad154)") (class "Default")
      (node (ref "U2") (pin "154") (pinfunction "I/O_(DOUT,_BUSY),_L12P_YY_154") (pintype "bidirectional+no_connect"))
    )
    (net (code "280") (name "unconnected-(U2A-I{slash}O_(IRDY),_L18N_YY-Pad132)") (class "Default")
      (node (ref "U2") (pin "132") (pinfunction "I/O_(IRDY),_L18N_YY_132") (pintype "bidirectional+no_connect"))
    )
    (net (code "281") (name "unconnected-(U2A-I{slash}O_(IRDY),_L44N_YY-Pad24)") (class "Default")
      (node (ref "U2") (pin "24") (pinfunction "I/O_(IRDY),_L44N_YY_24") (pintype "bidirectional+no_connect"))
    )
    (net (code "282") (name "unconnected-(U2A-I{slash}O_(TRDY)-Pad27)") (class "Default")
      (node (ref "U2") (pin "27") (pinfunction "I/O_(TRDY)_27") (pintype "bidirectional+no_connect"))
    )
    (net (code "283") (name "unconnected-(U2A-I{slash}O_(TRDY)-Pad129)") (class "Default")
      (node (ref "U2") (pin "129") (pinfunction "I/O_(TRDY)_129") (pintype "bidirectional+no_connect"))
    )
    (net (code "284") (name "unconnected-(U2A-I{slash}O_(~{CS}),_L11P_YY-Pad160)") (class "Default")
      (node (ref "U2") (pin "160") (pinfunction "I/O_(~{CS}),_L11P_YY_160") (pintype "bidirectional+no_connect"))
    )
    (net (code "285") (name "unconnected-(U2A-I{slash}O_(~{WRITE}),_L11N_YY-Pad161)") (class "Default")
      (node (ref "U2") (pin "161") (pinfunction "I/O_(~{WRITE}),_L11N_YY_161") (pintype "bidirectional+no_connect"))
    )
  )
)
